# 4GModule-MiniPCI-E.net
KiCad netlist of a schematic drawn in Altium Designer
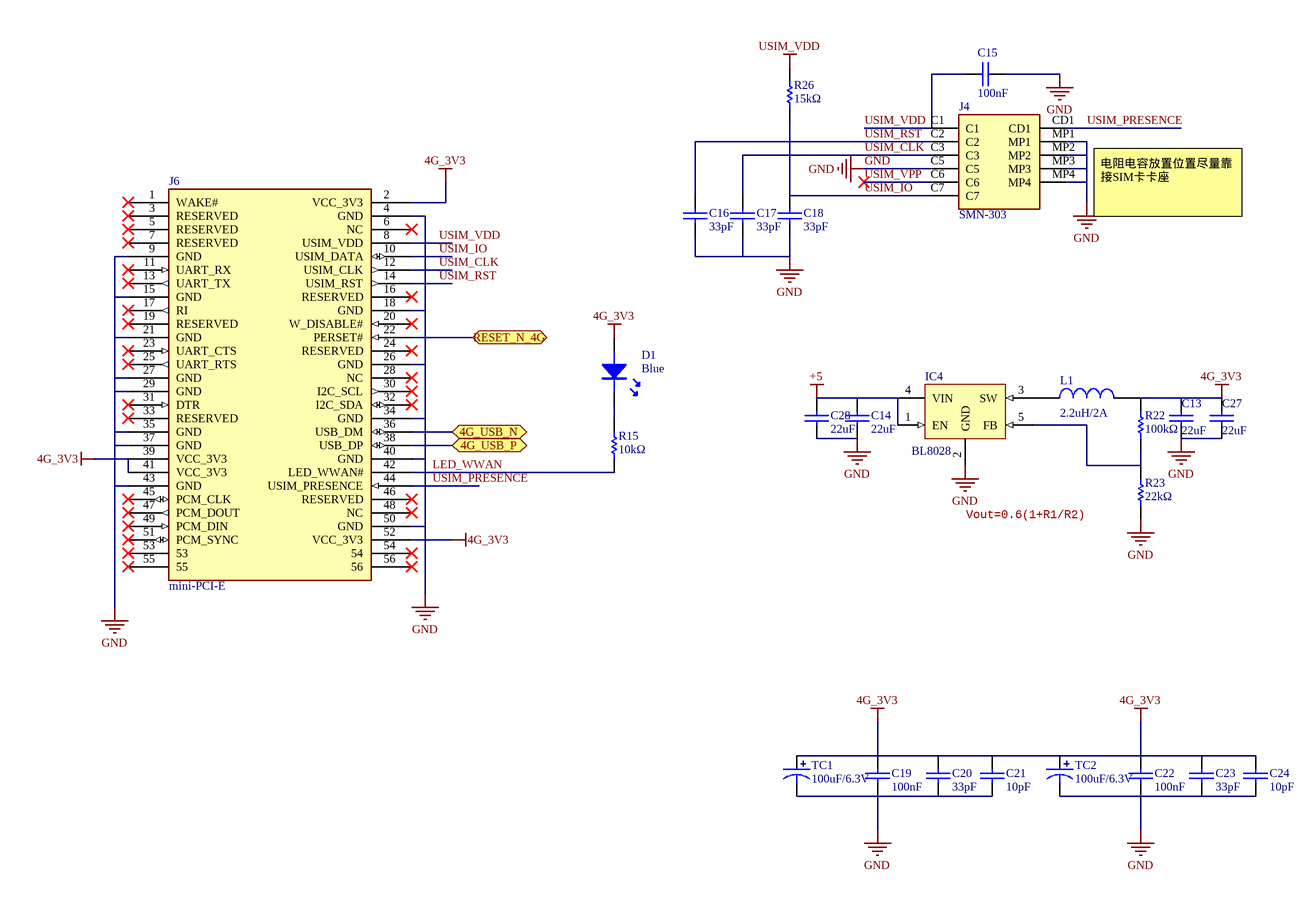
[diagram p0: 4GModule-MiniPCI-E.SchDoc]

(export (version "E")
  (design (tool "Eeschema 10.0.6"))
  (components
    (comp (ref "C13")
      (value "22uF")
      (footprint "C_0603")
      (description "贴片电容")
      (libsource (lib "IntLib-Passive") (part "Cap_Chip"))
    )
    (comp (ref "C14")
      (value "22uF")
      (footprint "C_0603")
      (description "贴片电容")
      (libsource (lib "IntLib-Passive") (part "Cap_Chip"))
    )
    (comp (ref "C15")
      (value "100nF")
      (footprint "C_0402")
      (description "贴片电容")
      (libsource (lib "IntLib-Passive") (part "Cap_Chip"))
    )
    (comp (ref "C16")
      (value "33pF")
      (footprint "C_0402")
      (description "贴片电容")
      (libsource (lib "IntLib-Passive") (part "Cap_Chip"))
    )
    (comp (ref "C17")
      (value "33pF")
      (footprint "C_0402")
      (description "贴片电容")
      (libsource (lib "IntLib-Passive") (part "Cap_Chip"))
    )
    (comp (ref "C18")
      (value "33pF")
      (footprint "C_0402")
      (description "贴片电容")
      (libsource (lib "IntLib-Passive") (part "Cap_Chip"))
    )
    (comp (ref "C19")
      (value "100nF")
      (footprint "C_0402")
      (description "贴片电容")
      (libsource (lib "IntLib-Passive") (part "Cap_Chip"))
    )
    (comp (ref "C20")
      (value "33pF")
      (footprint "C_0402")
      (description "贴片电容")
      (libsource (lib "IntLib-Passive") (part "Cap_Chip"))
    )
    (comp (ref "C21")
      (value "10pF")
      (footprint "C_0402")
      (description "贴片电容")
      (libsource (lib "IntLib-Passive") (part "Cap_Chip"))
    )
    (comp (ref "C22")
      (value "100nF")
      (footprint "C_0402")
      (description "贴片电容")
      (libsource (lib "IntLib-Passive") (part "Cap_Chip"))
    )
    (comp (ref "C23")
      (value "33pF")
      (footprint "C_0402")
      (description "贴片电容")
      (libsource (lib "IntLib-Passive") (part "Cap_Chip"))
    )
    (comp (ref "C24")
      (value "10pF")
      (footprint "C_0402")
      (description "贴片电容")
      (libsource (lib "IntLib-Passive") (part "Cap_Chip"))
    )
    (comp (ref "C27")
      (value "22uF")
      (footprint "C_0603")
      (description "贴片电容")
      (libsource (lib "IntLib-Passive") (part "Cap_Chip"))
    )
    (comp (ref "C28")
      (value "22uF")
      (footprint "C_0603")
      (description "贴片电容")
      (libsource (lib "IntLib-Passive") (part "Cap_Chip"))
    )
    (comp (ref "D1")
      (value "Blue")
      (footprint "LED-0603-B")
      (description "贴片LED")
      (libsource (lib "IntLib-Active") (part "LED_Chip"))
    )
    (comp (ref "IC4")
      (value "BL8028")
      (footprint "SOT23-5")
      (description "DC-DC 芯片")
      (libsource (lib "IntLib-IC") (part "BL8028"))
    )
    (comp (ref "J4")
      (value "SMN-303")
      (footprint "SimCard_SMN-303")
      (description "NANO SIM卡座")
      (libsource (lib "IntLib-Connector") (part "SimCard_Nano"))
    )
    (comp (ref "J6")
      (value "mini-PCI-E")
      (footprint "CardEdge_MINI-PCI-E-4H")
      (description "EC25 mini-PCI-E 座子")
      (libsource (lib "Connector-CardEdge") (part "CardEdge_MiniPCI-E"))
    )
    (comp (ref "L1")
      (value "2.2uH/2A")
      (footprint "L_1008")
      (description "小功率电感")
      (fields (field (name "MANUFACTURER_PART_NUMBER") "BDCD002520122R2MS1"))
      (libsource (lib "IntLib-Passive") (part "Ind_Chip"))
    )
    (comp (ref "R15")
      (value "10kΩ")
      (footprint "R_0402")
      (description "贴片电阻")
      (libsource (lib "IntLib-Passive") (part "Res_Chip"))
    )
    (comp (ref "R22")
      (value "100kΩ")
      (footprint "R_0402")
      (description "贴片电阻")
      (libsource (lib "IntLib-Passive") (part "Res_Chip"))
    )
    (comp (ref "R23")
      (value "22kΩ")
      (footprint "R_0402")
      (description "贴片电阻")
      (libsource (lib "IntLib-Passive") (part "Res_Chip"))
    )
    (comp (ref "R26")
      (value "15kΩ")
      (footprint "R_0402")
      (description "贴片电阻")
      (libsource (lib "IntLib-Passive") (part "Res_Chip"))
    )
    (comp (ref "TC1")
      (value "100uF/6.3V")
      (footprint "TAJ-B/3528")
      (description "钽电容")
      (libsource (lib "IntLib-Passive") (part "Cap_TAN"))
    )
    (comp (ref "TC2")
      (value "100uF/6.3V")
      (footprint "TAJ-B/3528")
      (description "钽电容")
      (libsource (lib "IntLib-Passive") (part "Cap_TAN"))
    )
  )
  (nets
    (net (code "1") (name "+5") (class "Default")
      (node (ref "C14") (pin "2") (pinfunction "2_2") (pintype "passive"))
      (node (ref "C28") (pin "2") (pinfunction "2_2") (pintype "passive"))
      (node (ref "IC4") (pin "1") (pinfunction "EN_1") (pintype "input"))
      (node (ref "IC4") (pin "4") (pinfunction "VIN_4") (pintype "power_in"))
    )
    (net (code "2") (name "/4G_USB_N") (class "Default")
      (node (ref "J6") (pin "36") (pinfunction "USB_DM_36") (pintype "bidirectional"))
    )
    (net (code "3") (name "/4G_USB_P") (class "Default")
      (node (ref "J6") (pin "38") (pinfunction "USB_DP_38") (pintype "bidirectional"))
    )
    (net (code "4") (name "/LED_WWAN") (class "Default")
      (node (ref "J6") (pin "42") (pinfunction "LED_WWAN#_42") (pintype "open_collector"))
      (node (ref "R15") (pin "1") (pinfunction "1_1") (pintype "passive"))
    )
    (net (code "5") (name "/RESET_N_4G") (class "Default")
      (node (ref "J6") (pin "22") (pinfunction "PERSET#_22") (pintype "input"))
    )
    (net (code "6") (name "/USIM_CLK") (class "Default")
      (node (ref "C17") (pin "2") (pinfunction "2_2") (pintype "passive"))
      (node (ref "J4") (pin "C3") (pinfunction "C3_C3") (pintype "passive"))
      (node (ref "J6") (pin "12") (pinfunction "USIM_CLK_12") (pintype "output"))
    )
    (net (code "7") (name "/USIM_IO") (class "Default")
      (node (ref "C18") (pin "2") (pinfunction "2_2") (pintype "passive"))
      (node (ref "J4") (pin "C7") (pinfunction "C7_C7") (pintype "passive"))
      (node (ref "J6") (pin "10") (pinfunction "USIM_DATA_10") (pintype "bidirectional"))
      (node (ref "R26") (pin "1") (pinfunction "1_1") (pintype "passive"))
    )
    (net (code "8") (name "/USIM_PRESENCE") (class "Default")
      (node (ref "J4") (pin "CD1") (pinfunction "CD1_CD1") (pintype "passive"))
      (node (ref "J6") (pin "44") (pinfunction "USIM_PRESENCE_44") (pintype "input"))
    )
    (net (code "9") (name "/USIM_RST") (class "Default")
      (node (ref "C16") (pin "2") (pinfunction "2_2") (pintype "passive"))
      (node (ref "J4") (pin "C2") (pinfunction "C2_C2") (pintype "passive"))
      (node (ref "J6") (pin "14") (pinfunction "USIM_RST_14") (pintype "output"))
    )
    (net (code "10") (name "/USIM_VPP") (class "Default")
      (node (ref "J4") (pin "C6") (pinfunction "C6_C6") (pintype "passive+no_connect"))
    )
    (net (code "11") (name "4G_3V3") (class "Default")
      (node (ref "C13") (pin "2") (pinfunction "2_2") (pintype "passive"))
      (node (ref "C19") (pin "2") (pinfunction "2_2") (pintype "passive"))
      (node (ref "C20") (pin "2") (pinfunction "2_2") (pintype "passive"))
      (node (ref "C21") (pin "2") (pinfunction "2_2") (pintype "passive"))
      (node (ref "C22") (pin "2") (pinfunction "2_2") (pintype "passive"))
      (node (ref "C23") (pin "2") (pinfunction "2_2") (pintype "passive"))
      (node (ref "C24") (pin "2") (pinfunction "2_2") (pintype "passive"))
      (node (ref "C27") (pin "2") (pinfunction "2_2") (pintype "passive"))
      (node (ref "D1") (pin "A") (pinfunction "A_A") (pintype "passive"))
      (node (ref "J6") (pin "2") (pinfunction "VCC_3V3_2") (pintype "power_in"))
      (node (ref "J6") (pin "39") (pinfunction "VCC_3V3_39") (pintype "power_in"))
      (node (ref "J6") (pin "41") (pinfunction "VCC_3V3_41") (pintype "power_in"))
      (node (ref "J6") (pin "52") (pinfunction "VCC_3V3_52") (pintype "passive"))
      (node (ref "L1") (pin "2") (pinfunction "2_2") (pintype "passive"))
      (node (ref "R22") (pin "2") (pinfunction "2_2") (pintype "passive"))
      (node (ref "TC1") (pin "1") (pinfunction "1_1") (pintype "passive"))
      (node (ref "TC2") (pin "1") (pinfunction "1_1") (pintype "passive"))
    )
    (net (code "12") (name "GND") (class "Default")
      (node (ref "C13") (pin "1") (pinfunction "1_1") (pintype "passive"))
      (node (ref "C14") (pin "1") (pinfunction "1_1") (pintype "passive"))
      (node (ref "C15") (pin "1") (pinfunction "1_1") (pintype "passive"))
      (node (ref "C16") (pin "1") (pinfunction "1_1") (pintype "passive"))
      (node (ref "C17") (pin "1") (pinfunction "1_1") (pintype "passive"))
      (node (ref "C18") (pin "1") (pinfunction "1_1") (pintype "passive"))
      (node (ref "C19") (pin "1") (pinfunction "1_1") (pintype "passive"))
      (node (ref "C20") (pin "1") (pinfunction "1_1") (pintype "passive"))
      (node (ref "C21") (pin "1") (pinfunction "1_1") (pintype "passive"))
      (node (ref "C22") (pin "1") (pinfunction "1_1") (pintype "passive"))
      (node (ref "C23") (pin "1") (pinfunction "1_1") (pintype "passive"))
      (node (ref "C24") (pin "1") (pinfunction "1_1") (pintype "passive"))
      (node (ref "C27") (pin "1") (pinfunction "1_1") (pintype "passive"))
      (node (ref "C28") (pin "1") (pinfunction "1_1") (pintype "passive"))
      (node (ref "IC4") (pin "2") (pinfunction "GND_2") (pintype "power_in"))
      (node (ref "J4") (pin "C5") (pinfunction "C5_C5") (pintype "passive"))
      (node (ref "J4") (pin "MP1") (pinfunction "MP1_MP1") (pintype "passive"))
      (node (ref "J4") (pin "MP2") (pinfunction "MP2_MP2") (pintype "passive"))
      (node (ref "J4") (pin "MP3") (pinfunction "MP3_MP3") (pintype "passive"))
      (node (ref "J4") (pin "MP4") (pinfunction "MP4_MP4") (pintype "passive"))
      (node (ref "J6") (pin "15") (pinfunction "GND_15") (pintype "power_in"))
      (node (ref "J6") (pin "18") (pinfunction "GND_18") (pintype "power_in"))
      (node (ref "J6") (pin "21") (pinfunction "GND_21") (pintype "power_in"))
      (node (ref "J6") (pin "26") (pinfunction "GND_26") (pintype "power_in"))
      (node (ref "J6") (pin "27") (pinfunction "GND_27") (pintype "power_in"))
      (node (ref "J6") (pin "29") (pinfunction "GND_29") (pintype "power_in"))
      (node (ref "J6") (pin "34") (pinfunction "GND_34") (pintype "power_in"))
      (node (ref "J6") (pin "35") (pinfunction "GND_35") (pintype "power_in"))
      (node (ref "J6") (pin "37") (pinfunction "GND_37") (pintype "power_in"))
      (node (ref "J6") (pin "4") (pinfunction "GND_4") (pintype "power_in"))
      (node (ref "J6") (pin "40") (pinfunction "GND_40") (pintype "power_in"))
      (node (ref "J6") (pin "43") (pinfunction "GND_43") (pintype "power_in"))
      (node (ref "J6") (pin "50") (pinfunction "GND_50") (pintype "power_in"))
      (node (ref "J6") (pin "9") (pinfunction "GND_9") (pintype "power_in"))
      (node (ref "R23") (pin "1") (pinfunction "1_1") (pintype "passive"))
      (node (ref "TC1") (pin "2") (pinfunction "2_2") (pintype "passive"))
      (node (ref "TC2") (pin "2") (pinfunction "2_2") (pintype "passive"))
    )
    (net (code "13") (name "Net-(D1-PadK)") (class "Default")
      (node (ref "D1") (pin "K") (pinfunction "K_K") (pintype "passive"))
      (node (ref "R15") (pin "2") (pinfunction "2_2") (pintype "passive"))
    )
    (net (code "14") (name "Net-(IC4-FB)") (class "Default")
      (node (ref "IC4") (pin "5") (pinfunction "FB_5") (pintype "input"))
      (node (ref "R22") (pin "1") (pinfunction "1_1") (pintype "passive"))
      (node (ref "R23") (pin "2") (pinfunction "2_2") (pintype "passive"))
    )
    (net (code "15") (name "Net-(IC4-SW)") (class "Default")
      (node (ref "IC4") (pin "3") (pinfunction "SW_3") (pintype "input"))
      (node (ref "L1") (pin "1") (pinfunction "1_1") (pintype "passive"))
    )
    (net (code "16") (name "USIM_VDD") (class "Default")
      (node (ref "C15") (pin "2") (pinfunction "2_2") (pintype "passive"))
      (node (ref "J4") (pin "C1") (pinfunction "C1_C1") (pintype "passive"))
      (node (ref "J6") (pin "8") (pinfunction "USIM_VDD_8") (pintype "power_in"))
      (node (ref "R26") (pin "2") (pinfunction "2_2") (pintype "passive"))
    )
    (net (code "17") (name "unconnected-(J6-DTR-Pad31)") (class "Default")
      (node (ref "J6") (pin "31") (pinfunction "DTR_31") (pintype "input+no_connect"))
    )
    (net (code "18") (name "unconnected-(J6-I2C_SCL-Pad30)") (class "Default")
      (node (ref "J6") (pin "30") (pinfunction "I2C_SCL_30") (pintype "output+no_connect"))
    )
    (net (code "19") (name "unconnected-(J6-I2C_SDA-Pad32)") (class "Default")
      (node (ref "J6") (pin "32") (pinfunction "I2C_SDA_32") (pintype "bidirectional+no_connect"))
    )
    (net (code "20") (name "unconnected-(J6-NC-Pad6)") (class "Default")
      (node (ref "J6") (pin "6") (pinfunction "NC_6") (pintype "passive+no_connect"))
    )
    (net (code "21") (name "unconnected-(J6-NC-Pad28)") (class "Default")
      (node (ref "J6") (pin "28") (pinfunction "NC_28") (pintype "passive+no_connect"))
    )
    (net (code "22") (name "unconnected-(J6-NC-Pad48)") (class "Default")
      (node (ref "J6") (pin "48") (pinfunction "NC_48") (pintype "power_in+no_connect"))
    )
    (net (code "23") (name "unconnected-(J6-PCM_CLK-Pad45)") (class "Default")
      (node (ref "J6") (pin "45") (pinfunction "PCM_CLK_45") (pintype "bidirectional+no_connect"))
    )
    (net (code "24") (name "unconnected-(J6-PCM_DIN-Pad49)") (class "Default")
      (node (ref "J6") (pin "49") (pinfunction "PCM_DIN_49") (pintype "input+no_connect"))
    )
    (net (code "25") (name "unconnected-(J6-PCM_DOUT-Pad47)") (class "Default")
      (node (ref "J6") (pin "47") (pinfunction "PCM_DOUT_47") (pintype "output+no_connect"))
    )
    (net (code "26") (name "unconnected-(J6-PCM_SYNC-Pad51)") (class "Default")
      (node (ref "J6") (pin "51") (pinfunction "PCM_SYNC_51") (pintype "bidirectional+no_connect"))
    )
    (net (code "27") (name "unconnected-(J6-Pad53)") (class "Default")
      (node (ref "J6") (pin "53") (pinfunction "53_53") (pintype "passive+no_connect"))
    )
    (net (code "28") (name "unconnected-(J6-Pad54)") (class "Default")
      (node (ref "J6") (pin "54") (pinfunction "54_54") (pintype "passive+no_connect"))
    )
    (net (code "29") (name "unconnected-(J6-Pad55)") (class "Default")
      (node (ref "J6") (pin "55") (pinfunction "55_55") (pintype "passive+no_connect"))
    )
    (net (code "30") (name "unconnected-(J6-Pad56)") (class "Default")
      (node (ref "J6") (pin "56") (pinfunction "56_56") (pintype "passive+no_connect"))
    )
    (net (code "31") (name "unconnected-(J6-RESERVED-Pad3)") (class "Default")
      (node (ref "J6") (pin "3") (pinfunction "RESERVED_3") (pintype "passive+no_connect"))
    )
    (net (code "32") (name "unconnected-(J6-RESERVED-Pad5)") (class "Default")
      (node (ref "J6") (pin "5") (pinfunction "RESERVED_5") (pintype "passive+no_connect"))
    )
    (net (code "33") (name "unconnected-(J6-RESERVED-Pad7)") (class "Default")
      (node (ref "J6") (pin "7") (pinfunction "RESERVED_7") (pintype "passive+no_connect"))
    )
    (net (code "34") (name "unconnected-(J6-RESERVED-Pad16)") (class "Default")
      (node (ref "J6") (pin "16") (pinfunction "RESERVED_16") (pintype "passive+no_connect"))
    )
    (net (code "35") (name "unconnected-(J6-RESERVED-Pad19)") (class "Default")
      (node (ref "J6") (pin "19") (pinfunction "RESERVED_19") (pintype "passive+no_connect"))
    )
    (net (code "36") (name "unconnected-(J6-RESERVED-Pad24)") (class "Default")
      (node (ref "J6") (pin "24") (pinfunction "RESERVED_24") (pintype "passive+no_connect"))
    )
    (net (code "37") (name "unconnected-(J6-RESERVED-Pad33)") (class "Default")
      (node (ref "J6") (pin "33") (pinfunction "RESERVED_33") (pintype "passive+no_connect"))
    )
    (net (code "38") (name "unconnected-(J6-RESERVED-Pad46)") (class "Default")
      (node (ref "J6") (pin "46") (pinfunction "RESERVED_46") (pintype "passive+no_connect"))
    )
    (net (code "39") (name "unconnected-(J6-RI-Pad17)") (class "Default")
      (node (ref "J6") (pin "17") (pinfunction "RI_17") (pintype "output+no_connect"))
    )
    (net (code "40") (name "unconnected-(J6-UART_CTS-Pad23)") (class "Default")
      (node (ref "J6") (pin "23") (pinfunction "UART_CTS_23") (pintype "input+no_connect"))
    )
    (net (code "41") (name "unconnected-(J6-UART_RTS-Pad25)") (class "Default")
      (node (ref "J6") (pin "25") (pinfunction "UART_RTS_25") (pintype "output+no_connect"))
    )
    (net (code "42") (name "unconnected-(J6-UART_RX-Pad11)") (class "Default")
      (node (ref "J6") (pin "11") (pinfunction "UART_RX_11") (pintype "input+no_connect"))
    )
    (net (code "43") (name "unconnected-(J6-UART_TX-Pad13)") (class "Default")
      (node (ref "J6") (pin "13") (pinfunction "UART_TX_13") (pintype "output+no_connect"))
    )
    (net (code "44") (name "unconnected-(J6-WAKE#-Pad1)") (class "Default")
      (node (ref "J6") (pin "1") (pinfunction "WAKE#_1") (pintype "open_collector+no_connect"))
    )
    (net (code "45") (name "unconnected-(J6-W_DISABLE#-Pad20)") (class "Default")
      (node (ref "J6") (pin "20") (pinfunction "W_DISABLE#_20") (pintype "input+no_connect"))
    )
  )
)
